# ATESLEME.net
KiCad netlist of a schematic drawn in EAGLE
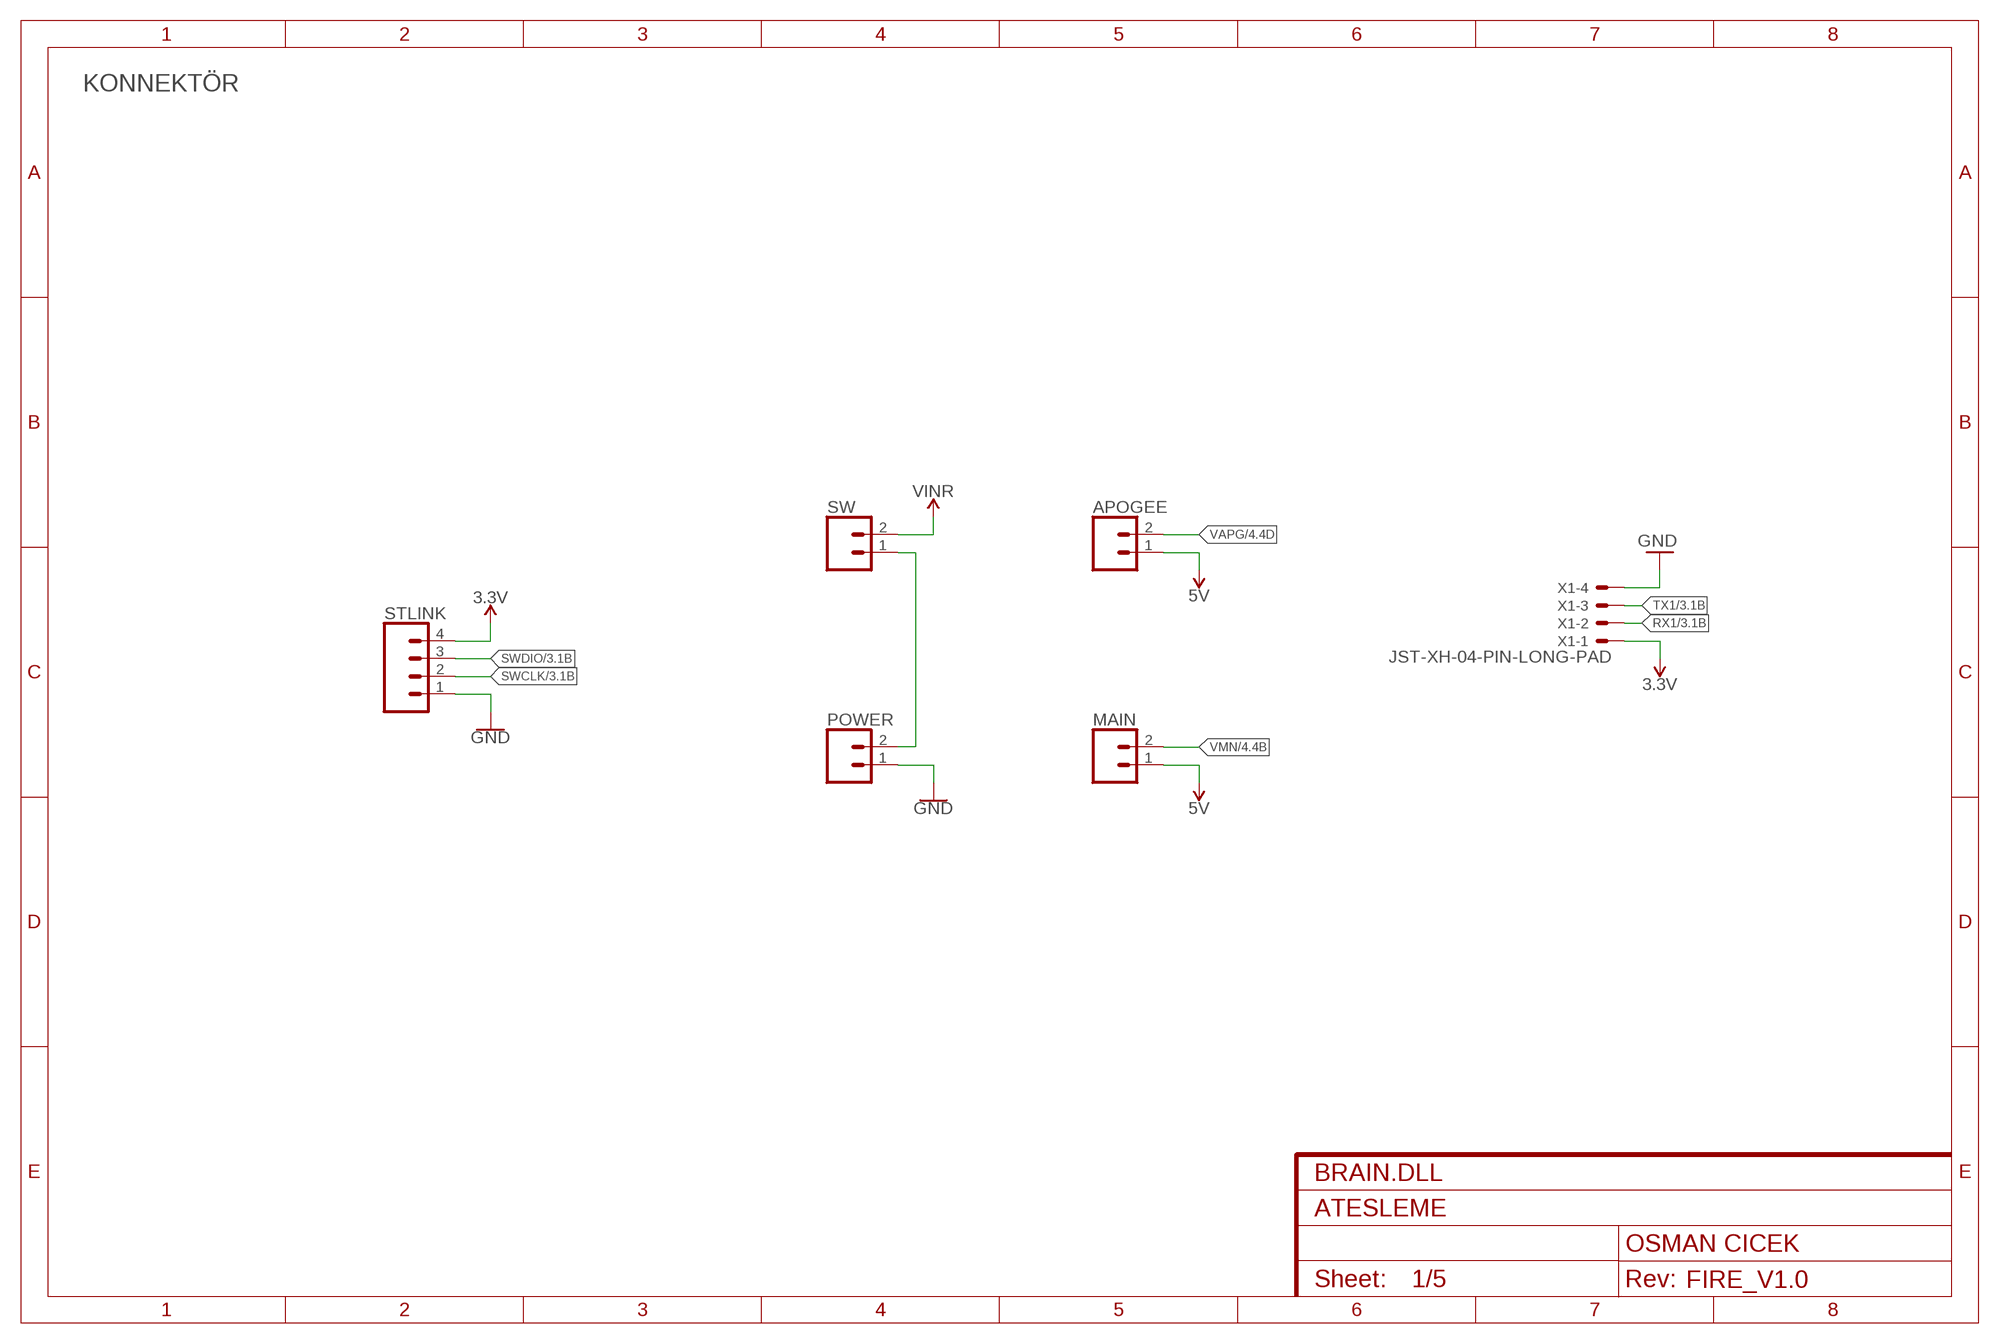
[diagram p0: schematic, sheet 1]
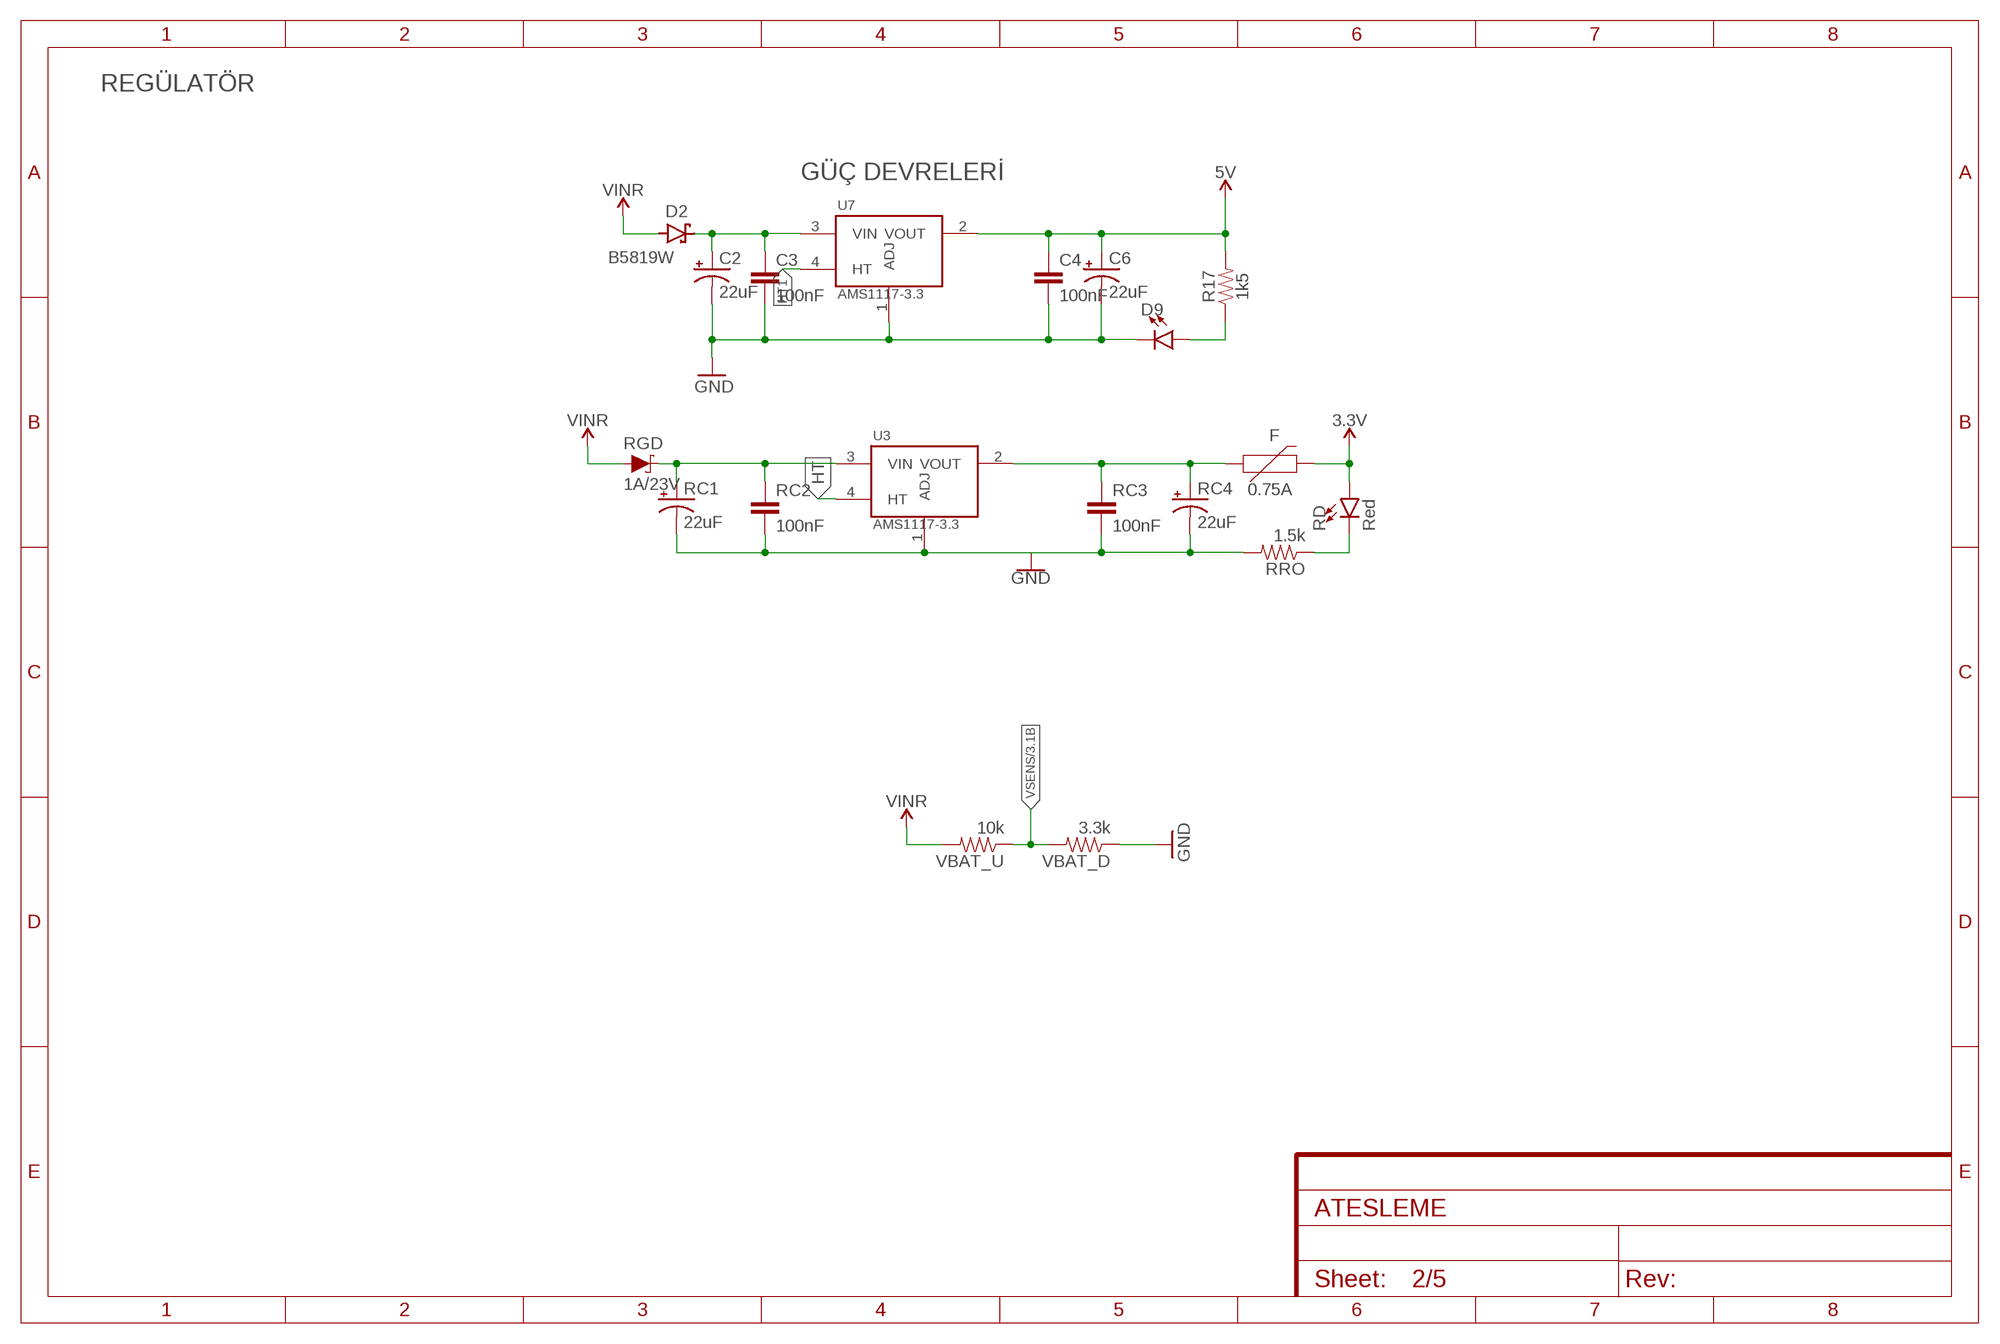
[diagram p1: schematic, sheet 2]
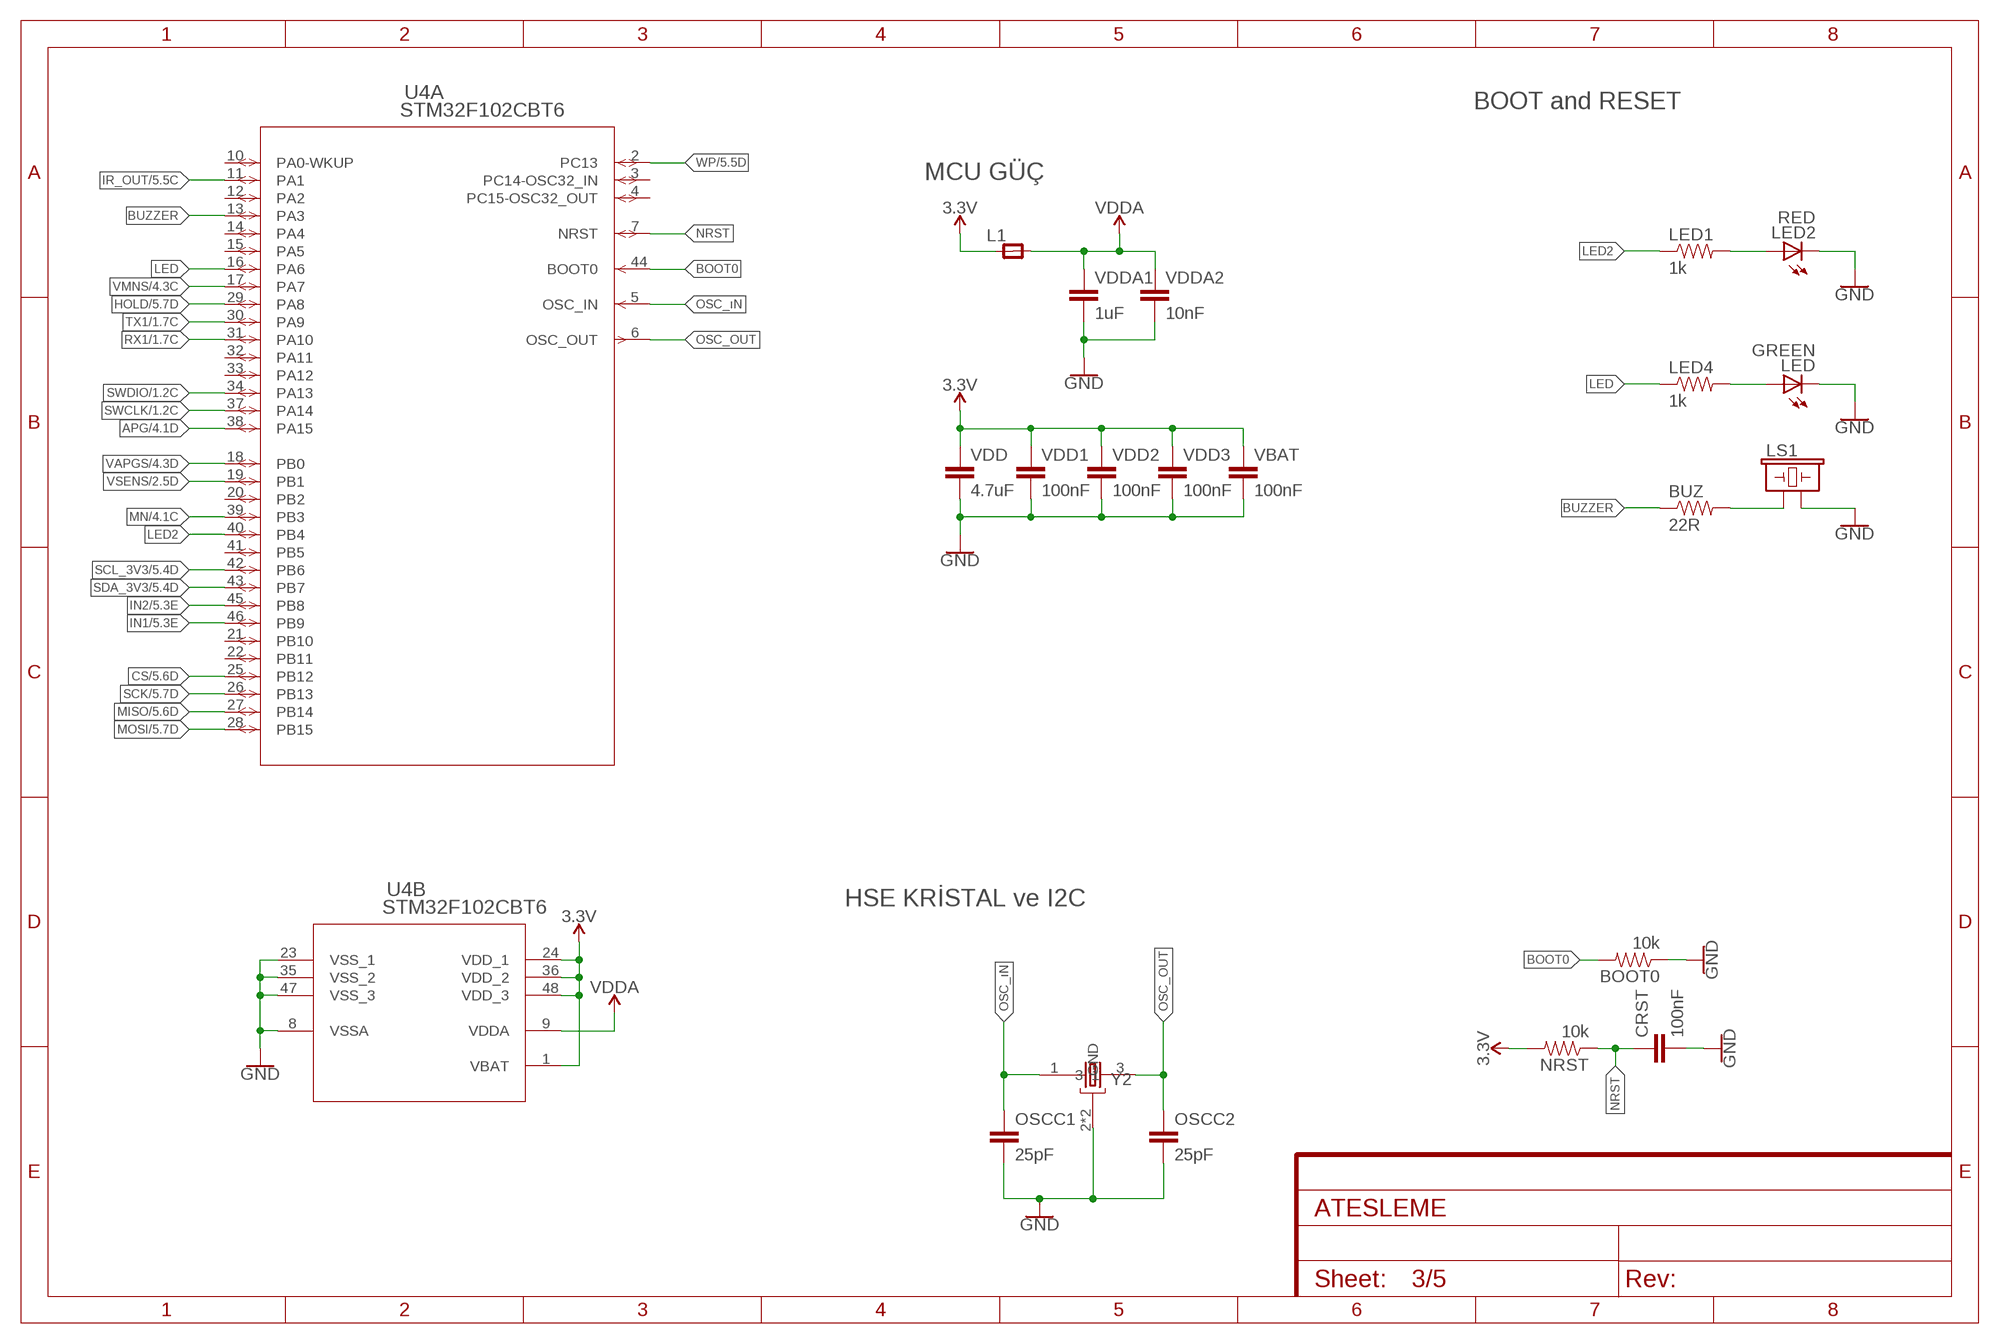
[diagram p2: schematic, sheet 3]
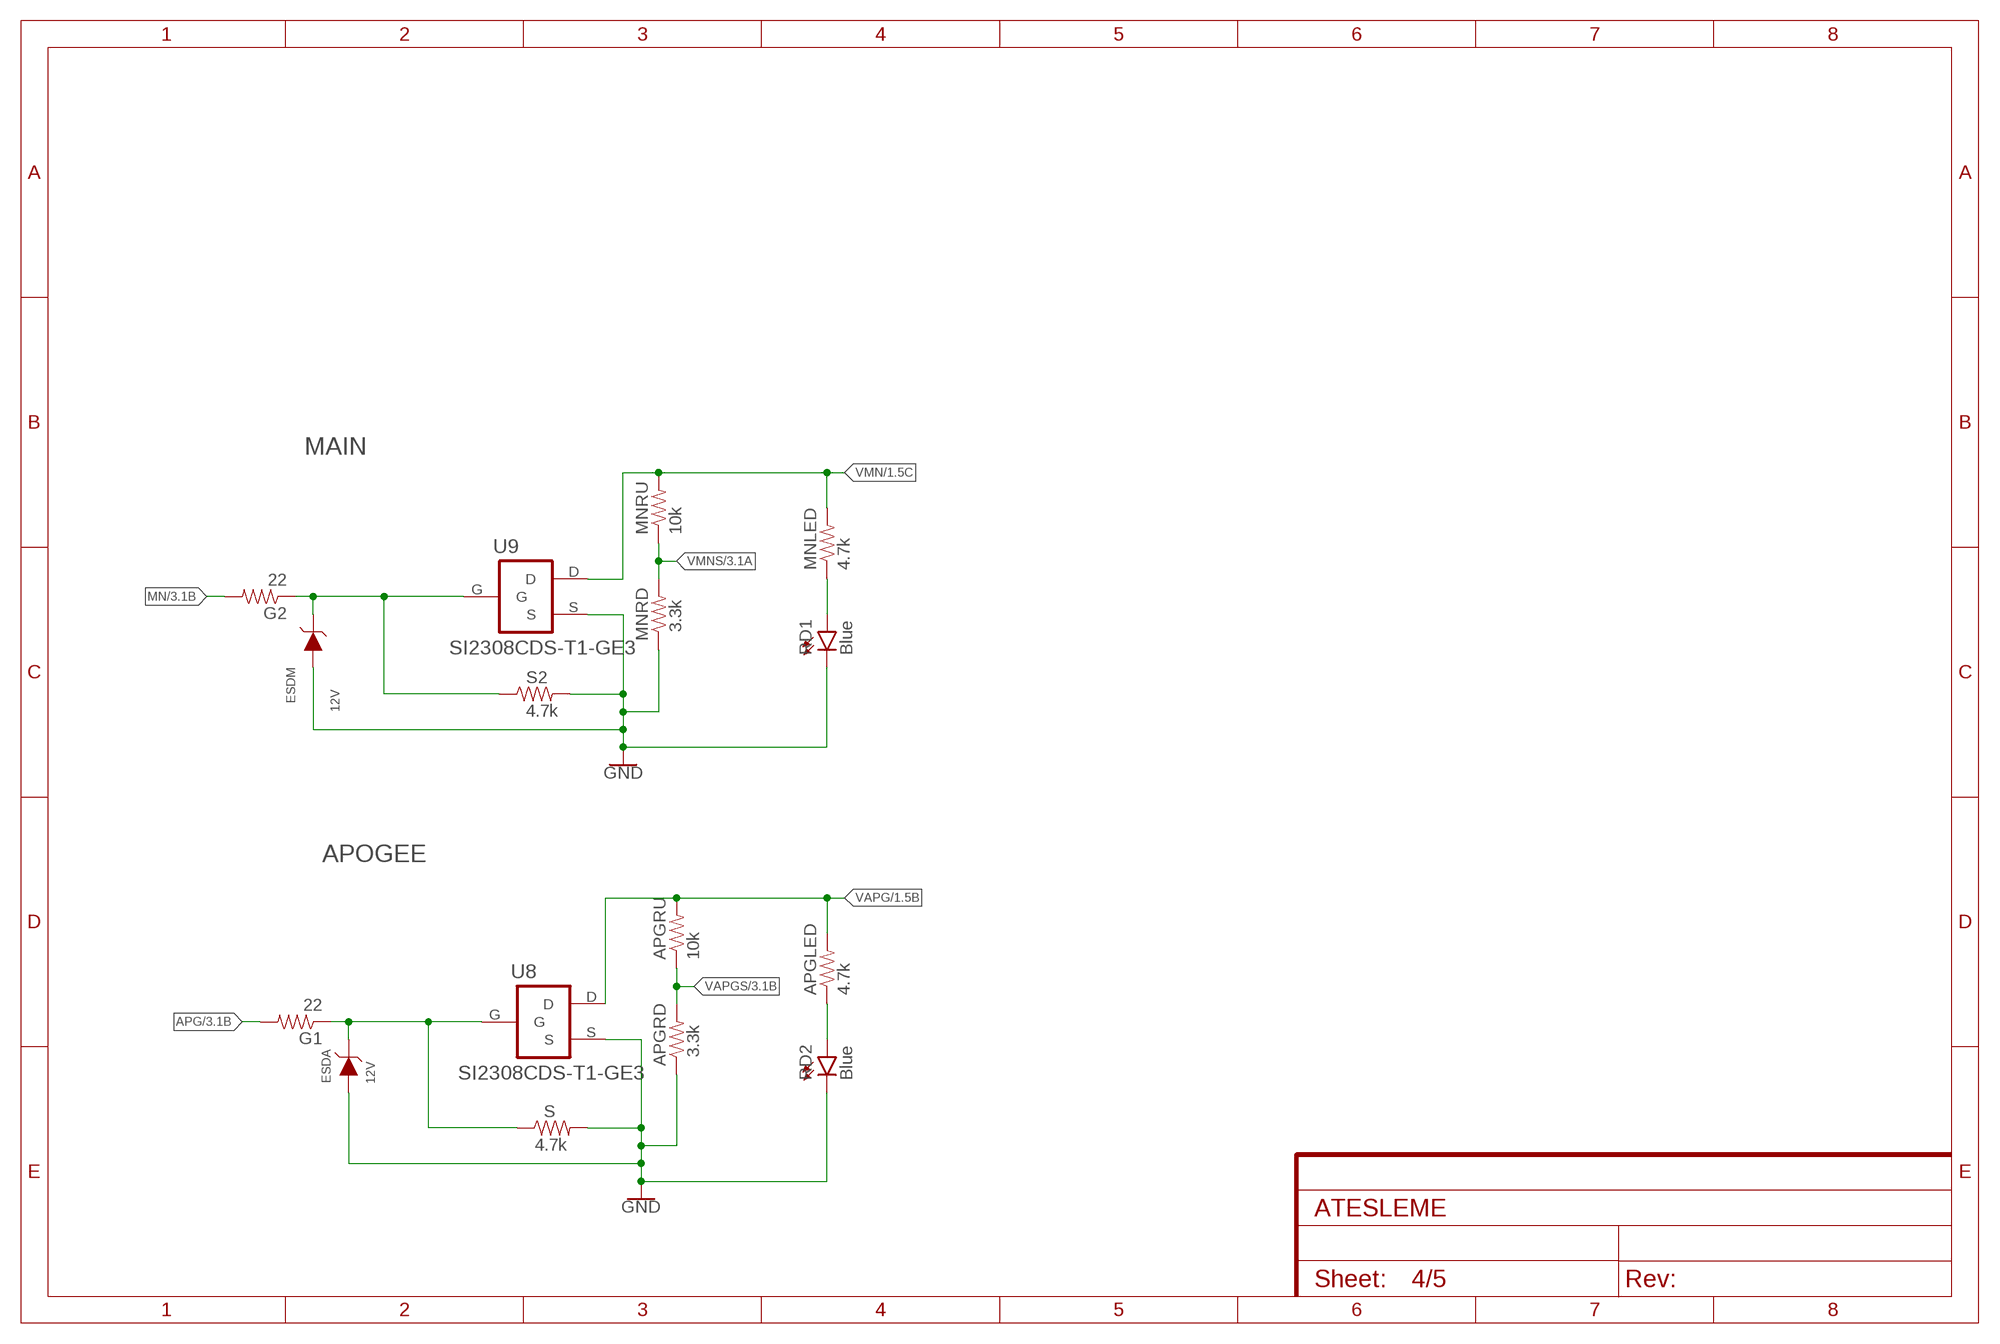
[diagram p3: schematic, sheet 4]
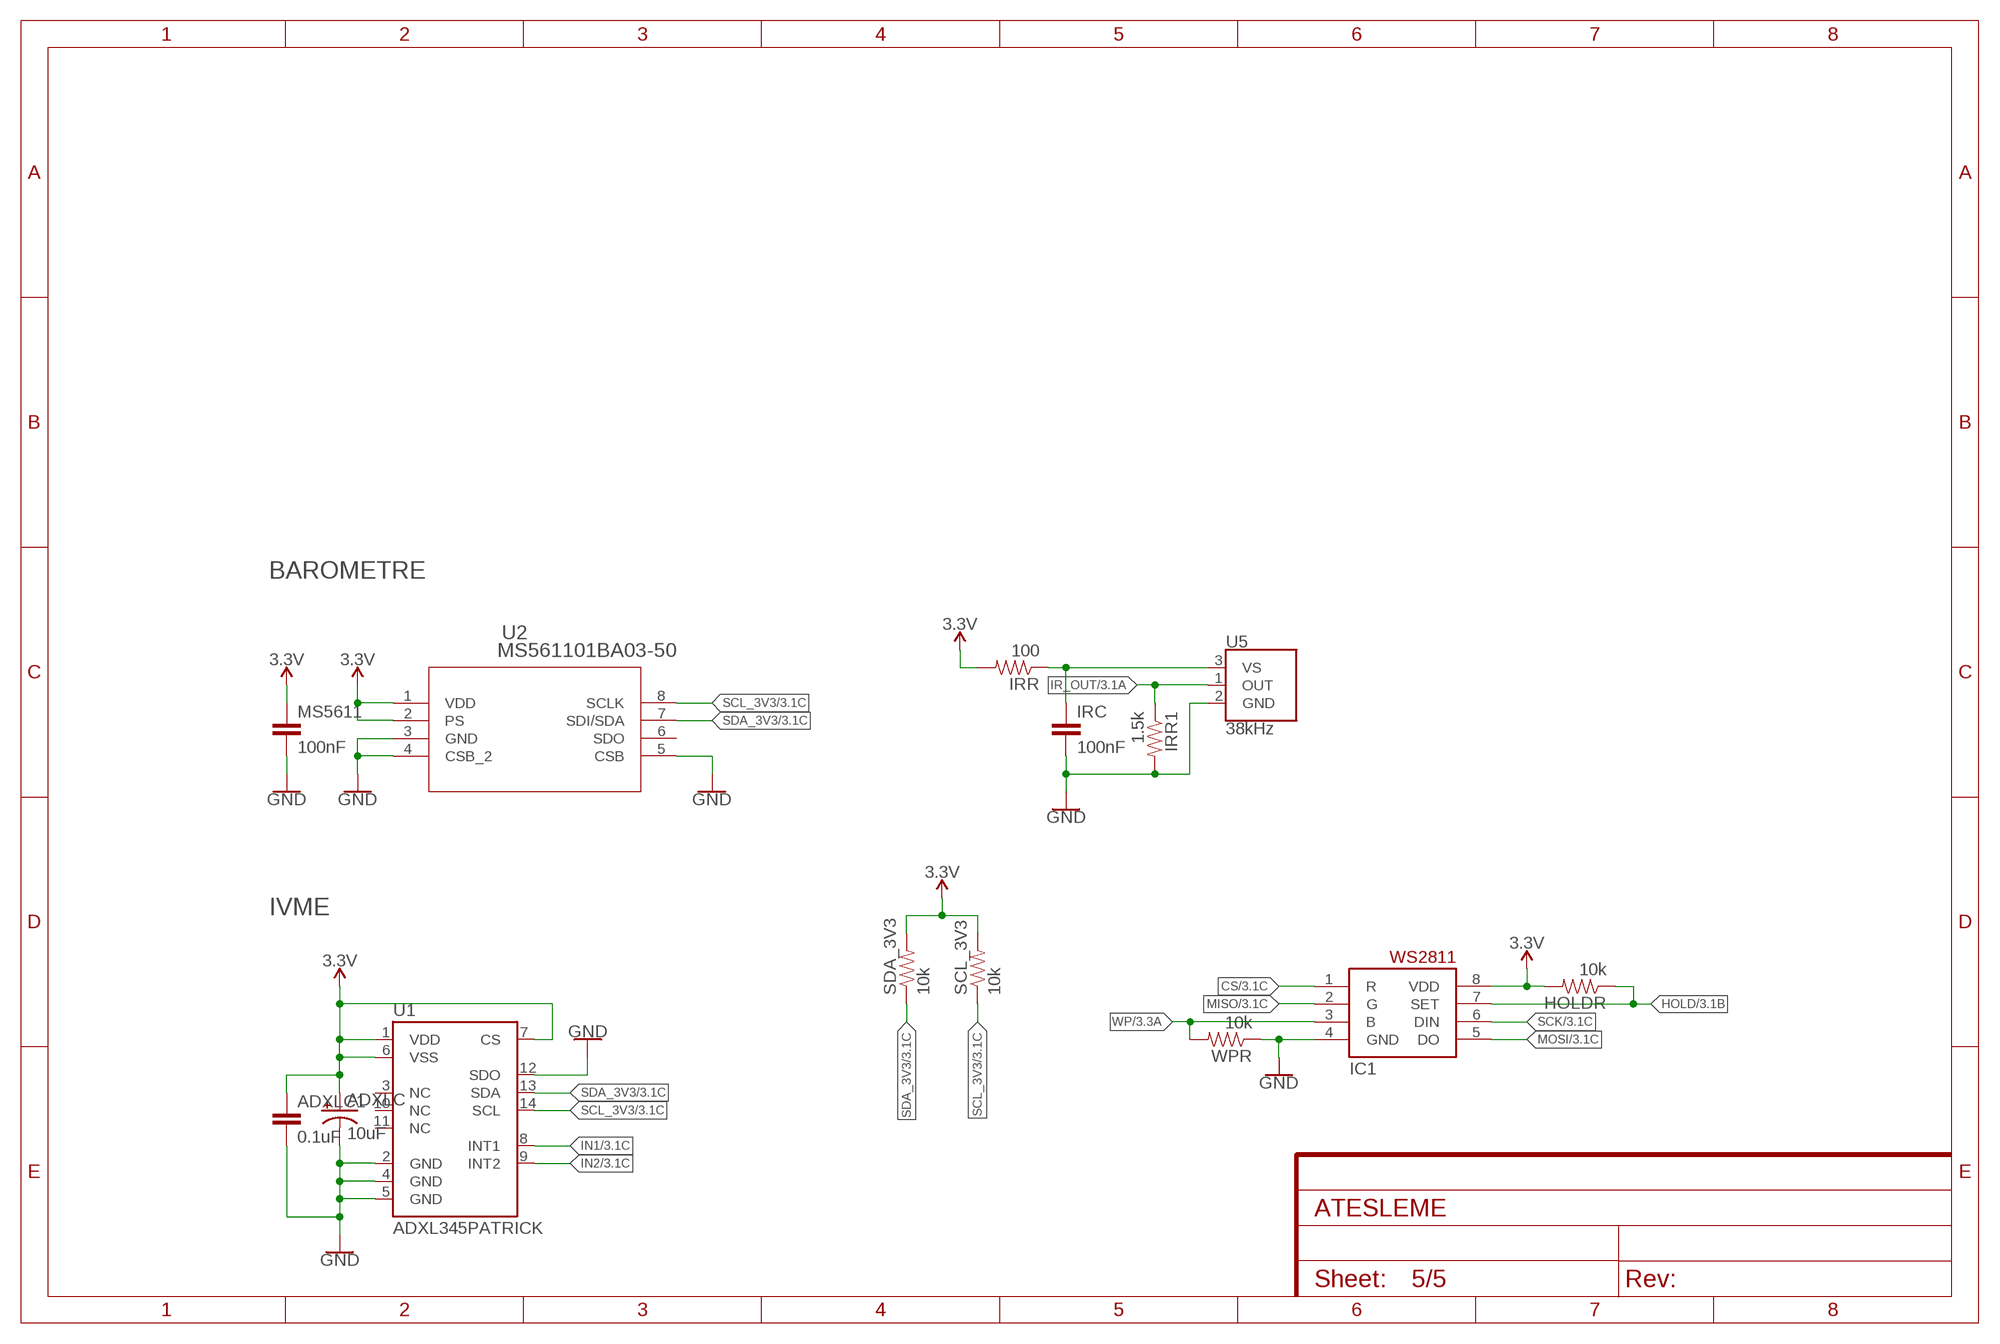
[diagram p4: schematic, sheet 5]

(export (version "E")
  (design (tool "Eeschema 10.0.6"))
  (components
    (comp (ref "APGLED")
      (value "4.7k")
      (footprint "eagle-import:0603-RES")
      (libsource (lib "eagle-import") (part "2.0KOHM1/10W5%(0603)"))
    )
    (comp (ref "APGRD")
      (value "3.3k")
      (footprint "eagle-import:0603-RES")
      (libsource (lib "eagle-import") (part "2.0KOHM1/10W5%(0603)"))
    )
    (comp (ref "APGRU")
      (value "10k")
      (footprint "eagle-import:0603-RES")
      (libsource (lib "eagle-import") (part "2.0KOHM1/10W5%(0603)"))
    )
    (comp (ref "ESDA")
      (value "12V")
      (footprint "eagle-import:WE-TVSP_DO-214AC_UNIDIRECTIONAL")
      (libsource (lib "eagle-import") (part "WE-TVSP_DO-214AC_400W_UNI_824500102"))
    )
    (comp (ref "ESDM")
      (value "12V")
      (footprint "eagle-import:WE-TVSP_DO-214AC_UNIDIRECTIONAL")
      (libsource (lib "eagle-import") (part "WE-TVSP_DO-214AC_400W_UNI_824500102"))
    )
    (comp (ref "G1")
      (value "22")
      (footprint "eagle-import:0603-RES")
      (libsource (lib "eagle-import") (part "2.0KOHM1/10W5%(0603)"))
    )
    (comp (ref "G2")
      (value "22")
      (footprint "eagle-import:0603-RES")
      (libsource (lib "eagle-import") (part "2.0KOHM1/10W5%(0603)"))
    )
    (comp (ref "MNLED")
      (value "4.7k")
      (footprint "eagle-import:0603-RES")
      (libsource (lib "eagle-import") (part "2.0KOHM1/10W5%(0603)"))
    )
    (comp (ref "MNRD")
      (value "3.3k")
      (footprint "eagle-import:0603-RES")
      (libsource (lib "eagle-import") (part "2.0KOHM1/10W5%(0603)"))
    )
    (comp (ref "MNRU")
      (value "10k")
      (footprint "eagle-import:0603-RES")
      (libsource (lib "eagle-import") (part "2.0KOHM1/10W5%(0603)"))
    )
    (comp (ref "RD1")
      (value "Blue")
      (footprint "eagle-import:LED-0603")
      (libsource (lib "eagle-import") (part "LED-RED0603-SMART"))
    )
    (comp (ref "RD2")
      (value "Blue")
      (footprint "eagle-import:LED-0603")
      (libsource (lib "eagle-import") (part "LED-RED0603-SMART"))
    )
    (comp (ref "S")
      (value "4.7k")
      (footprint "eagle-import:0603-RES")
      (libsource (lib "eagle-import") (part "2.0KOHM1/10W5%(0603)"))
    )
    (comp (ref "S2")
      (value "4.7k")
      (footprint "eagle-import:0603-RES")
      (libsource (lib "eagle-import") (part "2.0KOHM1/10W5%(0603)"))
    )
    (comp (ref "U8")
      (value "SI2308CDS-T1-GE3")
      (footprint "eagle-import:SOT95P240X112-3N")
      (fields (field (name "MF") "Infineon Technologies") (field (name "MP") "IRLML6344TRPBF"))
      (libsource (lib "eagle-import") (part "IRLML6344TRPBF"))
    )
    (comp (ref "U9")
      (value "SI2308CDS-T1-GE3")
      (footprint "eagle-import:SOT95P240X112-3N")
      (fields (field (name "MF") "Infineon Technologies") (field (name "MP") "IRLML6344TRPBF"))
      (libsource (lib "eagle-import") (part "IRLML6344TRPBF"))
    )
    (comp (ref "C2")
      (value "22uF")
      (footprint "eagle-import:EIA3528")
      (libsource (lib "eagle-import") (part "47UF-POLAR-EIA3528-10V-10%"))
    )
    (comp (ref "C3")
      (value "100nF")
      (footprint "eagle-import:0603")
      (libsource (lib "eagle-import") (part "1.0UF-0603-16V-10%"))
    )
    (comp (ref "C4")
      (value "100nF")
      (footprint "eagle-import:0603")
      (libsource (lib "eagle-import") (part "1.0UF-0603-16V-10%"))
    )
    (comp (ref "C6")
      (value "22uF")
      (footprint "eagle-import:EIA3528")
      (libsource (lib "eagle-import") (part "47UF-POLAR-EIA3528-10V-10%"))
    )
    (comp (ref "D2")
      (value "B5819W")
      (footprint "eagle-import:SODFL3718X115")
      (fields (field (name "MANUFACTURER") "ON Semiconductor") (field (name "MPN") "MBR0520LT1G"))
      (libsource (lib "eagle-import") (part "SCHOTTKY_DO-219MBR0520LT1G"))
    )
    (comp (ref "D9")
      (value "LED0603")
      (footprint "eagle-import:LED-0603")
      (libsource (lib "eagle-import") (part "LED0603"))
    )
    (comp (ref "F")
      (value "0.75A")
      (footprint "eagle-import:1206")
      (libsource (lib "eagle-import") (part "PPTC_THREE-QUARTER-AMP"))
    )
    (comp (ref "R17")
      (value "1k5")
      (footprint "eagle-import:0603")
      (libsource (lib "eagle-import") (part "1KOHM-0603-1/10W-1%"))
    )
    (comp (ref "RC1")
      (value "22uF")
      (footprint "eagle-import:EIA3528")
      (libsource (lib "eagle-import") (part "10UF-POLAR-EIA3528-20V-10%(TANT)"))
    )
    (comp (ref "RC2")
      (value "100nF")
      (footprint "eagle-import:0603")
      (libsource (lib "eagle-import") (part "0.1UF-0603-25V-(+80/-20%)"))
    )
    (comp (ref "RC3")
      (value "100nF")
      (footprint "eagle-import:0603")
      (libsource (lib "eagle-import") (part "0.1UF-0603-25V-(+80/-20%)"))
    )
    (comp (ref "RC4")
      (value "22uF")
      (footprint "eagle-import:EIA3528")
      (libsource (lib "eagle-import") (part "10UF-POLAR-EIA3528-20V-10%(TANT)"))
    )
    (comp (ref "RD")
      (value "Red")
      (footprint "eagle-import:LED-0603")
      (libsource (lib "eagle-import") (part "LED-RED0603-SMART"))
    )
    (comp (ref "RGD")
      (value "1A/23V")
      (footprint "eagle-import:SOD-323")
      (libsource (lib "eagle-import") (part "DIODE-SCHOTTKY-BAT20J"))
    )
    (comp (ref "RRO")
      (value "1.5k")
      (footprint "eagle-import:0603-RES")
      (libsource (lib "eagle-import") (part "2.0KOHM1/10W5%(0603)"))
    )
    (comp (ref "U3")
      (value "AMS1117-3.3")
      (footprint "eagle-import:SOT229P700X180-4N")
      (fields (field (name "MF") "Advanced Monolithic Systems"))
      (libsource (lib "eagle-import") (part "AMS1117-3.3"))
    )
    (comp (ref "U7")
      (value "AMS1117-3.3")
      (footprint "eagle-import:SOT229P700X180-4N")
      (fields (field (name "MF") "Advanced Monolithic Systems"))
      (libsource (lib "eagle-import") (part "AMS1117-3.3"))
    )
    (comp (ref "VBAT_D")
      (value "3.3k")
      (footprint "eagle-import:0603-RES")
      (libsource (lib "eagle-import") (part "2.0KOHM1/10W5%(0603)"))
    )
    (comp (ref "VBAT_U")
      (value "10k")
      (footprint "eagle-import:0603-RES")
      (libsource (lib "eagle-import") (part "2.0KOHM1/10W5%(0603)"))
    )
    (comp (ref "BOOT0")
      (value "10k")
      (footprint "eagle-import:0603-RES")
      (libsource (lib "eagle-import") (part "2.0KOHM1/10W5%(0603)"))
    )
    (comp (ref "BUZ")
      (value "22R")
      (footprint "eagle-import:0603-RES")
      (libsource (lib "eagle-import") (part "2.0KOHM1/10W5%(0603)"))
    )
    (comp (ref "CRST")
      (value "100nF")
      (footprint "eagle-import:0603")
      (libsource (lib "eagle-import") (part "0.1UF-0603-25V-(+80/-20%)"))
    )
    (comp (ref "L1")
      (value "RC-MASTER-SMD_FB_0805MP")
      (footprint "eagle-import:RC-MASTER-SMD_L0805MP")
      (libsource (lib "eagle-import") (part "RC-MASTER-SMD_FB_0805MP"))
    )
    (comp (ref "LED")
      (value "GREEN")
      (footprint "eagle-import:LED-0603")
      (libsource (lib "eagle-import") (part "LED-RED0603"))
    )
    (comp (ref "LED1")
      (value "1k")
      (footprint "eagle-import:0603-RES")
      (libsource (lib "eagle-import") (part "2.0KOHM1/10W5%(0603)"))
    )
    (comp (ref "LED2")
      (value "RED")
      (footprint "eagle-import:LED-0603")
      (libsource (lib "eagle-import") (part "LED-RED0603"))
    )
    (comp (ref "LED4")
      (value "1k")
      (footprint "eagle-import:0603-RES")
      (libsource (lib "eagle-import") (part "2.0KOHM1/10W5%(0603)"))
    )
    (comp (ref "LS1")
      (value "BUZZER-PTH")
      (footprint "eagle-import:BUZZER-12MM")
      (libsource (lib "eagle-import") (part "BUZZER-PTH"))
    )
    (comp (ref "NRST")
      (value "10k")
      (footprint "eagle-import:0603-RES")
      (libsource (lib "eagle-import") (part "2.0KOHM1/10W5%(0603)"))
    )
    (comp (ref "OSCC1")
      (value "25pF")
      (footprint "eagle-import:0603")
      (libsource (lib "eagle-import") (part "0.1UF-0603-25V-(+80/-20%)"))
    )
    (comp (ref "OSCC2")
      (value "25pF")
      (footprint "eagle-import:0603")
      (libsource (lib "eagle-import") (part "0.1UF-0603-25V-(+80/-20%)"))
    )
    (comp (ref "U4")
      (value "STM32F102CBT6")
      (footprint "eagle-import:LQFP48-7X7MM")
      (fields (field (name "COPYRIGHT") "Copyright (C) 2018 Accelerated Designs. All rights reserved"))
      (libsource (lib "eagle-import") (part "STM32F102CBT6"))
    )
    (comp (ref "VBAT")
      (value "100nF")
      (footprint "eagle-import:0603")
      (libsource (lib "eagle-import") (part "0.1UF-0603-25V-(+80/-20%)"))
    )
    (comp (ref "VDD")
      (value "4.7uF")
      (footprint "eagle-import:0603")
      (libsource (lib "eagle-import") (part "0.1UF-0603-25V-(+80/-20%)"))
    )
    (comp (ref "VDD1")
      (value "100nF")
      (footprint "eagle-import:0603")
      (libsource (lib "eagle-import") (part "0.1UF-0603-25V-(+80/-20%)"))
    )
    (comp (ref "VDD2")
      (value "100nF")
      (footprint "eagle-import:0603")
      (libsource (lib "eagle-import") (part "0.1UF-0603-25V-(+80/-20%)"))
    )
    (comp (ref "VDD3")
      (value "100nF")
      (footprint "eagle-import:0603")
      (libsource (lib "eagle-import") (part "0.1UF-0603-25V-(+80/-20%)"))
    )
    (comp (ref "VDDA1")
      (value "1uF")
      (footprint "eagle-import:0603")
      (libsource (lib "eagle-import") (part "0.1UF-0603-25V-(+80/-20%)"))
    )
    (comp (ref "VDDA2")
      (value "10nF")
      (footprint "eagle-import:0603")
      (libsource (lib "eagle-import") (part "0.1UF-0603-25V-(+80/-20%)"))
    )
    (comp (ref "Y2")
      (value "ABM2B-8.000MHZ-10-1-U-T")
      (footprint "eagle-import:OSCCC500X320X110-4N")
      (fields (field (name "MF") "Abracon") (field (name "MP") "ABM3B-26.000MHZ-10-1-U-T"))
      (libsource (lib "eagle-import") (part "ABM3B-26.000MHZ-10-1-U-T"))
    )
    (comp (ref "ADXLC")
      (value "10uF")
      (footprint "eagle-import:EIA3216")
      (libsource (lib "eagle-import") (part "10UF-POLAR-EIA3216-16V-10%(TANT)"))
    )
    (comp (ref "ADXLC1")
      (value "0.1uF")
      (footprint "eagle-import:0603")
      (libsource (lib "eagle-import") (part "0.1UF-0603-25V-(+80/-20%)"))
    )
    (comp (ref "HOLDR")
      (value "10k")
      (footprint "eagle-import:0603-RES")
      (libsource (lib "eagle-import") (part "2.0KOHM1/10W5%(0603)"))
    )
    (comp (ref "IC1")
      (value "EN25F40-100GCP-TR")
      (footprint "eagle-import:SO08-SKINNYPADS")
      (libsource (lib "eagle-import") (part "WS2811-SOP8"))
    )
    (comp (ref "IRC")
      (value "100nF")
      (footprint "eagle-import:0603")
      (libsource (lib "eagle-import") (part "0.1UF-0603-25V-(+80/-20%)"))
    )
    (comp (ref "IRR")
      (value "100")
      (footprint "eagle-import:0603-RES")
      (libsource (lib "eagle-import") (part "2.0KOHM1/10W5%(0603)"))
    )
    (comp (ref "IRR1")
      (value "1.5k")
      (footprint "eagle-import:0603-RES")
      (libsource (lib "eagle-import") (part "2.0KOHM1/10W5%(0603)"))
    )
    (comp (ref "MS5611")
      (value "100nF")
      (footprint "eagle-import:0603")
      (libsource (lib "eagle-import") (part "0.1UF-0603-25V-(+80/-20%)"))
    )
    (comp (ref "SCL_3V3")
      (value "10k")
      (footprint "eagle-import:0603-RES")
      (libsource (lib "eagle-import") (part "2.0KOHM1/10W5%(0603)"))
    )
    (comp (ref "SDA_3V3")
      (value "10k")
      (footprint "eagle-import:0603-RES")
      (libsource (lib "eagle-import") (part "2.0KOHM1/10W5%(0603)"))
    )
    (comp (ref "U1")
      (value "ADXL345PATRICK")
      (footprint "eagle-import:LGA14_1_1_PATRICK")
      (libsource (lib "eagle-import") (part "ADXL345PATRICK"))
    )
    (comp (ref "U2")
      (value "MS561101BA03-50")
      (footprint "eagle-import:SON8_MS5611_TEC")
      (fields (field (name "COPYRIGHT") "Copyright (C) 2016 Accelerated Designs. All rights reserved"))
      (libsource (lib "eagle-import") (part "MS561101BA03-50"))
    )
    (comp (ref "U5")
      (value "38kHz")
      (footprint "eagle-import:TSOP382")
      (libsource (lib "eagle-import") (part "TSOP38238"))
    )
    (comp (ref "WPR")
      (value "10k")
      (footprint "eagle-import:0603-RES")
      (libsource (lib "eagle-import") (part "2.0KOHM1/10W5%(0603)"))
    )
    (comp (ref "APOGEE")
      (value "CONN_023.5MM-NO_SILK")
      (footprint "eagle-import:SCREWTERMINAL-3.5MM-2-NS")
      (libsource (lib "eagle-import") (part "CONN_023.5MM-NO_SILK"))
    )
    (comp (ref "MAIN")
      (value "CONN_023.5MM-NO_SILK")
      (footprint "eagle-import:SCREWTERMINAL-3.5MM-2-NS")
      (libsource (lib "eagle-import") (part "CONN_023.5MM-NO_SILK"))
    )
    (comp (ref "POWER")
      (value "CONN_023.5MM-NO_SILK")
      (footprint "eagle-import:SCREWTERMINAL-3.5MM-2-NS")
      (libsource (lib "eagle-import") (part "CONN_023.5MM-NO_SILK"))
    )
    (comp (ref "STLINK")
      (value "CONN_04")
      (footprint "eagle-import:1X04")
      (libsource (lib "eagle-import") (part "CONN_04"))
    )
    (comp (ref "SW")
      (value "CONN_023.5MM-NO_SILK")
      (footprint "eagle-import:SCREWTERMINAL-3.5MM-2-NS")
      (libsource (lib "eagle-import") (part "CONN_023.5MM-NO_SILK"))
    )
    (comp (ref "X1")
      (value "JST-XH-04-PIN-LONG-PAD")
      (footprint "eagle-import:JST-XH-04-PACKAGE-LONG-PAD")
      (libsource (lib "eagle-import") (part "JST-XH-04-PIN-LONG-PAD"))
    )
  )
  (nets
    (net (code "1") (name "3.3V") (class "Default")
      (node (ref "ADXLC") (pin "+") (pinfunction "+_+") (pintype "passive"))
      (node (ref "ADXLC1") (pin "1") (pinfunction "1_1") (pintype "passive"))
      (node (ref "F") (pin "2") (pinfunction "2_2") (pintype "bidirectional"))
      (node (ref "HOLDR") (pin "2") (pinfunction "2_2") (pintype "passive"))
      (node (ref "IC1") (pin "8") (pinfunction "VDD_8") (pintype "power_in"))
      (node (ref "IRR") (pin "2") (pinfunction "2_2") (pintype "passive"))
      (node (ref "L1") (pin "1") (pinfunction "1_1") (pintype "passive"))
      (node (ref "MS5611") (pin "1") (pinfunction "1_1") (pintype "passive"))
      (node (ref "NRST") (pin "2") (pinfunction "2_2") (pintype "passive"))
      (node (ref "RD") (pin "A") (pinfunction "A_A") (pintype "passive"))
      (node (ref "SCL_3V3") (pin "2") (pinfunction "2_2") (pintype "passive"))
      (node (ref "SDA_3V3") (pin "2") (pinfunction "2_2") (pintype "passive"))
      (node (ref "STLINK") (pin "4") (pinfunction "4_4") (pintype "passive"))
      (node (ref "U1") (pin "1") (pinfunction "VDD_1") (pintype "bidirectional"))
      (node (ref "U1") (pin "6") (pinfunction "VSS_6") (pintype "bidirectional"))
      (node (ref "U1") (pin "7") (pinfunction "CS_7") (pintype "bidirectional"))
      (node (ref "U2") (pin "1") (pinfunction "VDD_1") (pintype "power_in"))
      (node (ref "U2") (pin "2") (pinfunction "PS_2") (pintype "input"))
      (node (ref "U4") (pin "1") (pinfunction "VBAT_1") (pintype "power_in"))
      (node (ref "U4") (pin "24") (pinfunction "VDD_1_24") (pintype "power_in"))
      (node (ref "U4") (pin "36") (pinfunction "VDD_2_36") (pintype "power_in"))
      (node (ref "U4") (pin "48") (pinfunction "VDD_3_48") (pintype "power_in"))
      (node (ref "VBAT") (pin "1") (pinfunction "1_1") (pintype "passive"))
      (node (ref "VDD") (pin "1") (pinfunction "1_1") (pintype "passive"))
      (node (ref "VDD1") (pin "1") (pinfunction "1_1") (pintype "passive"))
      (node (ref "VDD2") (pin "1") (pinfunction "1_1") (pintype "passive"))
      (node (ref "VDD3") (pin "1") (pinfunction "1_1") (pintype "passive"))
      (node (ref "X1") (pin "1") (pinfunction "S_1") (pintype "passive"))
    )
    (net (code "2") (name "5V") (class "Default")
      (node (ref "APOGEE") (pin "1") (pinfunction "1_1") (pintype "passive"))
      (node (ref "C4") (pin "1") (pinfunction "1_1") (pintype "passive"))
      (node (ref "C6") (pin "A") (pinfunction "+_A") (pintype "passive"))
      (node (ref "MAIN") (pin "1") (pinfunction "1_1") (pintype "passive"))
      (node (ref "R17") (pin "2") (pinfunction "2_2") (pintype "passive"))
      (node (ref "U7") (pin "2") (pinfunction "VOUT_2") (pintype "output"))
    )
    (net (code "3") (name "APG") (class "Default")
      (node (ref "G1") (pin "2") (pinfunction "2_2") (pintype "passive"))
      (node (ref "U4") (pin "38") (pinfunction "PA15_38") (pintype "bidirectional"))
    )
    (net (code "4") (name "BOOT0") (class "Default")
      (node (ref "BOOT0") (pin "2") (pinfunction "2_2") (pintype "passive"))
      (node (ref "U4") (pin "44") (pinfunction "BOOT0_44") (pintype "input"))
    )
    (net (code "5") (name "BUZZER") (class "Default")
      (node (ref "BUZ") (pin "1") (pinfunction "1_1") (pintype "passive"))
      (node (ref "U4") (pin "13") (pinfunction "PA3_13") (pintype "bidirectional"))
    )
    (net (code "6") (name "CS") (class "Default")
      (node (ref "IC1") (pin "1") (pinfunction "R_1") (pintype "open_collector"))
      (node (ref "U4") (pin "25") (pinfunction "PB12_25") (pintype "bidirectional"))
    )
    (net (code "7") (name "GND") (class "Default")
      (node (ref "ADXLC") (pin "-") (pinfunction "-_-") (pintype "passive"))
      (node (ref "ADXLC1") (pin "2") (pinfunction "2_2") (pintype "passive"))
      (node (ref "APGRD") (pin "1") (pinfunction "1_1") (pintype "passive"))
      (node (ref "BOOT0") (pin "1") (pinfunction "1_1") (pintype "passive"))
      (node (ref "C2") (pin "C") (pinfunction "-_C") (pintype "passive"))
      (node (ref "C3") (pin "2") (pinfunction "2_2") (pintype "passive"))
      (node (ref "C4") (pin "2") (pinfunction "2_2") (pintype "passive"))
      (node (ref "C6") (pin "C") (pinfunction "-_C") (pintype "passive"))
      (node (ref "CRST") (pin "2") (pinfunction "2_2") (pintype "passive"))
      (node (ref "D9") (pin "C") (pinfunction "C_C") (pintype "passive"))
      (node (ref "ESDA") (pin "2") (pinfunction "A_2") (pintype "passive"))
      (node (ref "ESDM") (pin "2") (pinfunction "A_2") (pintype "passive"))
      (node (ref "IC1") (pin "4") (pinfunction "GND_4") (pintype "power_in"))
      (node (ref "IRC") (pin "2") (pinfunction "2_2") (pintype "passive"))
      (node (ref "IRR1") (pin "2") (pinfunction "2_2") (pintype "passive"))
      (node (ref "LED") (pin "C") (pinfunction "C_C") (pintype "passive"))
      (node (ref "LED2") (pin "C") (pinfunction "C_C") (pintype "passive"))
      (node (ref "LS1") (pin "-") (pinfunction "2_-") (pintype "passive"))
      (node (ref "MNRD") (pin "1") (pinfunction "1_1") (pintype "passive"))
      (node (ref "MS5611") (pin "2") (pinfunction "2_2") (pintype "passive"))
      (node (ref "OSCC1") (pin "2") (pinfunction "2_2") (pintype "passive"))
      (node (ref "OSCC2") (pin "2") (pinfunction "2_2") (pintype "passive"))
      (node (ref "POWER") (pin "1") (pinfunction "1_1") (pintype "passive"))
      (node (ref "RC1") (pin "C") (pinfunction "-_C") (pintype "passive"))
      (node (ref "RC2") (pin "2") (pinfunction "2_2") (pintype "passive"))
      (node (ref "RC3") (pin "2") (pinfunction "2_2") (pintype "passive"))
      (node (ref "RC4") (pin "C") (pinfunction "-_C") (pintype "passive"))
      (node (ref "RD1") (pin "C") (pinfunction "C_C") (pintype "passive"))
      (node (ref "RD2") (pin "C") (pinfunction "C_C") (pintype "passive"))
      (node (ref "RRO") (pin "2") (pinfunction "2_2") (pintype "passive"))
      (node (ref "S") (pin "2") (pinfunction "2_2") (pintype "passive"))
      (node (ref "S2") (pin "2") (pinfunction "2_2") (pintype "passive"))
      (node (ref "STLINK") (pin "1") (pinfunction "1_1") (pintype "passive"))
      (node (ref "U1") (pin "12") (pinfunction "SDO_12") (pintype "bidirectional"))
      (node (ref "U1") (pin "2") (pinfunction "GND_2") (pintype "bidirectional"))
      (node (ref "U1") (pin "4") (pinfunction "GND_4") (pintype "bidirectional"))
      (node (ref "U1") (pin "5") (pinfunction "GND_5") (pintype "bidirectional"))
      (node (ref "U2") (pin "3") (pinfunction "GND_3") (pintype "passive"))
      (node (ref "U2") (pin "4") (pinfunction "CSB_2_4") (pintype "input"))
      (node (ref "U2") (pin "5") (pinfunction "CSB_5") (pintype "input"))
      (node (ref "U3") (pin "1") (pinfunction "ADJ_1") (pintype "power_in"))
      (node (ref "U4") (pin "23") (pinfunction "VSS_1_23") (pintype "power_in"))
      (node (ref "U4") (pin "35") (pinfunction "VSS_2_35") (pintype "power_in"))
      (node (ref "U4") (pin "47") (pinfunction "VSS_3_47") (pintype "power_in"))
      (node (ref "U4") (pin "8") (pinfunction "VSSA_8") (pintype "power_in"))
      (node (ref "U5") (pin "2") (pinfunction "GND_2") (pintype "bidirectional"))
      (node (ref "U7") (pin "1") (pinfunction "ADJ_1") (pintype "power_in"))
      (node (ref "U8") (pin "S") (pinfunction "S_S") (pintype "passive"))
      (node (ref "U9") (pin "S") (pinfunction "S_S") (pintype "passive"))
      (node (ref "VBAT") (pin "2") (pinfunction "2_2") (pintype "passive"))
      (node (ref "VBAT_D") (pin "1") (pinfunction "1_1") (pintype "passive"))
      (node (ref "VDD") (pin "2") (pinfunction "2_2") (pintype "passive"))
      (node (ref "VDD1") (pin "2") (pinfunction "2_2") (pintype "passive"))
      (node (ref "VDD2") (pin "2") (pinfunction "2_2") (pintype "passive"))
      (node (ref "VDD3") (pin "2") (pinfunction "2_2") (pintype "passive"))
      (node (ref "VDDA1") (pin "2") (pinfunction "2_2") (pintype "passive"))
      (node (ref "VDDA2") (pin "2") (pinfunction "2_2") (pintype "passive"))
      (node (ref "WPR") (pin "1") (pinfunction "1_1") (pintype "passive"))
      (node (ref "X1") (pin "4") (pinfunction "S_4") (pintype "passive"))
      (node (ref "Y2") (pin "2") (pinfunction "GND_2") (pintype "passive"))
      (node (ref "Y2") (pin "4") (pinfunction "GND_4") (pintype "passive"))
    )
    (net (code "8") (name "HOLD") (class "Default")
      (node (ref "HOLDR") (pin "1") (pinfunction "1_1") (pintype "passive"))
      (node (ref "IC1") (pin "7") (pinfunction "SET_7") (pintype "input"))
      (node (ref "U4") (pin "29") (pinfunction "PA8_29") (pintype "bidirectional"))
    )
    (net (code "9") (name "HT") (class "Default")
      (node (ref "U3") (pin "4") (pinfunction "HT_4") (pintype "bidirectional"))
    )
    (net (code "10") (name "HT1") (class "Default")
      (node (ref "U7") (pin "4") (pinfunction "HT_4") (pintype "bidirectional"))
    )
    (net (code "11") (name "IN1") (class "Default")
      (node (ref "U1") (pin "8") (pinfunction "INT1_8") (pintype "bidirectional"))
      (node (ref "U4") (pin "46") (pinfunction "PB9_46") (pintype "bidirectional"))
    )
    (net (code "12") (name "IN2") (class "Default")
      (node (ref "U1") (pin "9") (pinfunction "INT2_9") (pintype "bidirectional"))
      (node (ref "U4") (pin "45") (pinfunction "PB8_45") (pintype "bidirectional"))
    )
    (net (code "13") (name "IR_OUT") (class "Default")
      (node (ref "IRR1") (pin "1") (pinfunction "1_1") (pintype "passive"))
      (node (ref "U4") (pin "11") (pinfunction "PA1_11") (pintype "bidirectional"))
      (node (ref "U5") (pin "1") (pinfunction "OUT_1") (pintype "bidirectional"))
    )
    (net (code "14") (name "LED") (class "Default")
      (node (ref "LED4") (pin "1") (pinfunction "1_1") (pintype "passive"))
      (node (ref "U4") (pin "16") (pinfunction "PA6_16") (pintype "bidirectional"))
    )
    (net (code "15") (name "LED2") (class "Default")
      (node (ref "LED1") (pin "1") (pinfunction "1_1") (pintype "passive"))
      (node (ref "U4") (pin "40") (pinfunction "PB4_40") (pintype "bidirectional"))
    )
    (net (code "16") (name "MISO") (class "Default")
      (node (ref "IC1") (pin "2") (pinfunction "G_2") (pintype "open_collector"))
      (node (ref "U4") (pin "27") (pinfunction "PB14_27") (pintype "bidirectional"))
    )
    (net (code "17") (name "MN") (class "Default")
      (node (ref "G2") (pin "2") (pinfunction "2_2") (pintype "passive"))
      (node (ref "U4") (pin "39") (pinfunction "PB3_39") (pintype "bidirectional"))
    )
    (net (code "18") (name "MOSI") (class "Default")
      (node (ref "IC1") (pin "5") (pinfunction "DO_5") (pintype "output"))
      (node (ref "U4") (pin "28") (pinfunction "PB15_28") (pintype "bidirectional"))
    )
    (net (code "19") (name "NRST") (class "Default")
      (node (ref "CRST") (pin "1") (pinfunction "1_1") (pintype "passive"))
      (node (ref "NRST") (pin "1") (pinfunction "1_1") (pintype "passive"))
      (node (ref "U4") (pin "7") (pinfunction "NRST_7") (pintype "bidirectional"))
    )
    (net (code "20") (name "Net-(APGLED-Pad1)") (class "Default")
      (node (ref "APGLED") (pin "1") (pinfunction "1_1") (pintype "passive"))
      (node (ref "RD2") (pin "A") (pinfunction "A_A") (pintype "passive"))
    )
    (net (code "21") (name "Net-(C2-+)") (class "Default")
      (node (ref "C2") (pin "A") (pinfunction "+_A") (pintype "passive"))
      (node (ref "C3") (pin "1") (pinfunction "1_1") (pintype "passive"))
      (node (ref "D2") (pin "1") (pinfunction "C_1") (pintype "passive"))
      (node (ref "U7") (pin "3") (pinfunction "VIN_3") (pintype "input"))
    )
    (net (code "22") (name "Net-(D9-PadA)") (class "Default")
      (node (ref "D9") (pin "A") (pinfunction "A_A") (pintype "passive"))
      (node (ref "R17") (pin "1") (pinfunction "1_1") (pintype "passive"))
    )
    (net (code "23") (name "Net-(ESDA-C)") (class "Default")
      (node (ref "ESDA") (pin "1") (pinfunction "C_1") (pintype "passive"))
      (node (ref "G1") (pin "1") (pinfunction "1_1") (pintype "passive"))
      (node (ref "S") (pin "1") (pinfunction "1_1") (pintype "passive"))
      (node (ref "U8") (pin "G") (pinfunction "G_G") (pintype "input"))
    )
    (net (code "24") (name "Net-(ESDM-C)") (class "Default")
      (node (ref "ESDM") (pin "1") (pinfunction "C_1") (pintype "passive"))
      (node (ref "G2") (pin "1") (pinfunction "1_1") (pintype "passive"))
      (node (ref "S2") (pin "1") (pinfunction "1_1") (pintype "passive"))
      (node (ref "U9") (pin "G") (pinfunction "G_G") (pintype "input"))
    )
    (net (code "25") (name "Net-(LED-PadA)") (class "Default")
      (node (ref "LED") (pin "A") (pinfunction "A_A") (pintype "passive"))
      (node (ref "LED4") (pin "2") (pinfunction "2_2") (pintype "passive"))
    )
    (net (code "26") (name "Net-(LED1-Pad2)") (class "Default")
      (node (ref "LED1") (pin "2") (pinfunction "2_2") (pintype "passive"))
      (node (ref "LED2") (pin "A") (pinfunction "A_A") (pintype "passive"))
    )
    (net (code "27") (name "Net-(LS1-1)") (class "Default")
      (node (ref "BUZ") (pin "2") (pinfunction "2_2") (pintype "passive"))
      (node (ref "LS1") (pin "+") (pinfunction "1_+") (pintype "passive"))
    )
    (net (code "28") (name "Net-(MNLED-Pad1)") (class "Default")
      (node (ref "MNLED") (pin "1") (pinfunction "1_1") (pintype "passive"))
      (node (ref "RD1") (pin "A") (pinfunction "A_A") (pintype "passive"))
    )
    (net (code "29") (name "Net-(POWER-Pad2)") (class "Default")
      (node (ref "POWER") (pin "2") (pinfunction "2_2") (pintype "passive"))
      (node (ref "SW") (pin "1") (pinfunction "1_1") (pintype "passive"))
    )
    (net (code "30") (name "Net-(RC1-+)") (class "Default")
      (node (ref "RC1") (pin "A") (pinfunction "+_A") (pintype "passive"))
      (node (ref "RC2") (pin "1") (pinfunction "1_1") (pintype "passive"))
      (node (ref "RGD") (pin "C") (pinfunction "C_C") (pintype "passive"))
      (node (ref "U3") (pin "3") (pinfunction "VIN_3") (pintype "input"))
    )
    (net (code "31") (name "Net-(RC4-+)") (class "Default")
      (node (ref "F") (pin "1") (pinfunction "1_1") (pintype "bidirectional"))
      (node (ref "RC3") (pin "1") (pinfunction "1_1") (pintype "passive"))
      (node (ref "RC4") (pin "A") (pinfunction "+_A") (pintype "passive"))
      (node (ref "U3") (pin "2") (pinfunction "VOUT_2") (pintype "output"))
    )
    (net (code "32") (name "Net-(RD-PadC)") (class "Default")
      (node (ref "RD") (pin "C") (pinfunction "C_C") (pintype "passive"))
      (node (ref "RRO") (pin "1") (pinfunction "1_1") (pintype "passive"))
    )
    (net (code "33") (name "Net-(U5-VS)") (class "Default")
      (node (ref "IRC") (pin "1") (pinfunction "1_1") (pintype "passive"))
      (node (ref "IRR") (pin "1") (pinfunction "1_1") (pintype "passive"))
      (node (ref "U5") (pin "3") (pinfunction "VS_3") (pintype "bidirectional"))
    )
    (net (code "34") (name "OSC_OUT") (class "Default")
      (node (ref "OSCC2") (pin "1") (pinfunction "1_1") (pintype "passive"))
      (node (ref "U4") (pin "6") (pinfunction "OSC_OUT_6") (pintype "output"))
      (node (ref "Y2") (pin "3") (pinfunction "3_3") (pintype "passive"))
    )
    (net (code "35") (name "OSC_ıN") (class "Default")
      (node (ref "OSCC1") (pin "1") (pinfunction "1_1") (pintype "passive"))
      (node (ref "U4") (pin "5") (pinfunction "OSC_IN_5") (pintype "input"))
      (node (ref "Y2") (pin "1") (pinfunction "1_1") (pintype "passive"))
    )
    (net (code "36") (name "RX1") (class "Default")
      (node (ref "U4") (pin "31") (pinfunction "PA10_31") (pintype "bidirectional"))
      (node (ref "X1") (pin "2") (pinfunction "S_2") (pintype "passive"))
    )
    (net (code "37") (name "SCK") (class "Default")
      (node (ref "IC1") (pin "6") (pinfunction "DIN_6") (pintype "input"))
      (node (ref "U4") (pin "26") (pinfunction "PB13_26") (pintype "bidirectional"))
    )
    (net (code "38") (name "SCL_3V3") (class "Default")
      (node (ref "SCL_3V3") (pin "1") (pinfunction "1_1") (pintype "passive"))
      (node (ref "U1") (pin "14") (pinfunction "SCL_14") (pintype "bidirectional"))
      (node (ref "U2") (pin "8") (pinfunction "SCLK_8") (pintype "input"))
      (node (ref "U4") (pin "42") (pinfunction "PB6_42") (pintype "bidirectional"))
    )
    (net (code "39") (name "SDA_3V3") (class "Default")
      (node (ref "SDA_3V3") (pin "1") (pinfunction "1_1") (pintype "passive"))
      (node (ref "U1") (pin "13") (pinfunction "SDA_13") (pintype "bidirectional"))
      (node (ref "U2") (pin "7") (pinfunction "SDI/SDA_7") (pintype "bidirectional"))
      (node (ref "U4") (pin "43") (pinfunction "PB7_43") (pintype "bidirectional"))
    )
    (net (code "40") (name "SWCLK") (class "Default")
      (node (ref "STLINK") (pin "2") (pinfunction "2_2") (pintype "passive"))
      (node (ref "U4") (pin "37") (pinfunction "PA14_37") (pintype "bidirectional"))
    )
    (net (code "41") (name "SWDIO") (class "Default")
      (node (ref "STLINK") (pin "3") (pinfunction "3_3") (pintype "passive"))
      (node (ref "U4") (pin "34") (pinfunction "PA13_34") (pintype "bidirectional"))
    )
    (net (code "42") (name "TX1") (class "Default")
      (node (ref "U4") (pin "30") (pinfunction "PA9_30") (pintype "bidirectional"))
      (node (ref "X1") (pin "3") (pinfunction "S_3") (pintype "passive"))
    )
    (net (code "43") (name "VAPG") (class "Default")
      (node (ref "APGLED") (pin "2") (pinfunction "2_2") (pintype "passive"))
      (node (ref "APGRU") (pin "2") (pinfunction "2_2") (pintype "passive"))
      (node (ref "APOGEE") (pin "2") (pinfunction "2_2") (pintype "passive"))
      (node (ref "U8") (pin "D") (pinfunction "D_D") (pintype "output"))
    )
    (net (code "44") (name "VAPGS") (class "Default")
      (node (ref "APGRD") (pin "2") (pinfunction "2_2") (pintype "passive"))
      (node (ref "APGRU") (pin "1") (pinfunction "1_1") (pintype "passive"))
      (node (ref "U4") (pin "18") (pinfunction "PB0_18") (pintype "bidirectional"))
    )
    (net (code "45") (name "VDDA") (class "Default")
      (node (ref "L1") (pin "2") (pinfunction "2_2") (pintype "passive"))
      (node (ref "U4") (pin "9") (pinfunction "VDDA_9") (pintype "power_in"))
      (node (ref "VDDA1") (pin "1") (pinfunction "1_1") (pintype "passive"))
      (node (ref "VDDA2") (pin "1") (pinfunction "1_1") (pintype "passive"))
    )
    (net (code "46") (name "VIN") (class "Default")
      (node (ref "D2") (pin "2") (pinfunction "A_2") (pintype "passive"))
      (node (ref "RGD") (pin "A") (pinfunction "A_A") (pintype "passive"))
      (node (ref "SW") (pin "2") (pinfunction "2_2") (pintype "passive"))
      (node (ref "VBAT_U") (pin "2") (pinfunction "2_2") (pintype "passive"))
    )
    (net (code "47") (name "VMN") (class "Default")
      (node (ref "MAIN") (pin "2") (pinfunction "2_2") (pintype "passive"))
      (node (ref "MNLED") (pin "2") (pinfunction "2_2") (pintype "passive"))
      (node (ref "MNRU") (pin "2") (pinfunction "2_2") (pintype "passive"))
      (node (ref "U9") (pin "D") (pinfunction "D_D") (pintype "output"))
    )
    (net (code "48") (name "VMNS") (class "Default")
      (node (ref "MNRD") (pin "2") (pinfunction "2_2") (pintype "passive"))
      (node (ref "MNRU") (pin "1") (pinfunction "1_1") (pintype "passive"))
      (node (ref "U4") (pin "17") (pinfunction "PA7_17") (pintype "bidirectional"))
    )
    (net (code "49") (name "VSENS") (class "Default")
      (node (ref "U4") (pin "19") (pinfunction "PB1_19") (pintype "bidirectional"))
      (node (ref "VBAT_D") (pin "2") (pinfunction "2_2") (pintype "passive"))
      (node (ref "VBAT_U") (pin "1") (pinfunction "1_1") (pintype "passive"))
    )
    (net (code "50") (name "WP") (class "Default")
      (node (ref "IC1") (pin "3") (pinfunction "B_3") (pintype "open_collector"))
      (node (ref "U4") (pin "2") (pinfunction "PC13_2") (pintype "bidirectional"))
      (node (ref "WPR") (pin "2") (pinfunction "2_2") (pintype "passive"))
    )
    (net (code "51") (name "unconnected-(U1-NC-Pad3)") (class "Default")
      (node (ref "U1") (pin "3") (pinfunction "NC_3") (pintype "bidirectional"))
    )
    (net (code "52") (name "unconnected-(U1-NC-Pad10)") (class "Default")
      (node (ref "U1") (pin "10") (pinfunction "NC_10") (pintype "bidirectional"))
    )
    (net (code "53") (name "unconnected-(U1-NC-Pad11)") (class "Default")
      (node (ref "U1") (pin "11") (pinfunction "NC_11") (pintype "bidirectional"))
    )
    (net (code "54") (name "unconnected-(U2-SDO-Pad6)") (class "Default")
      (node (ref "U2") (pin "6") (pinfunction "SDO_6") (pintype "output"))
    )
    (net (code "55") (name "unconnected-(U4A-PA0-WKUP-Pad10)") (class "Default")
      (node (ref "U4") (pin "10") (pinfunction "PA0-WKUP_10") (pintype "bidirectional"))
    )
    (net (code "56") (name "unconnected-(U4A-PA2-Pad12)") (class "Default")
      (node (ref "U4") (pin "12") (pinfunction "PA2_12") (pintype "bidirectional"))
    )
    (net (code "57") (name "unconnected-(U4A-PA4-Pad14)") (class "Default")
      (node (ref "U4") (pin "14") (pinfunction "PA4_14") (pintype "bidirectional"))
    )
    (net (code "58") (name "unconnected-(U4A-PA5-Pad15)") (class "Default")
      (node (ref "U4") (pin "15") (pinfunction "PA5_15") (pintype "bidirectional"))
    )
    (net (code "59") (name "unconnected-(U4A-PA11-Pad32)") (class "Default")
      (node (ref "U4") (pin "32") (pinfunction "PA11_32") (pintype "bidirectional"))
    )
    (net (code "60") (name "unconnected-(U4A-PA12-Pad33)") (class "Default")
      (node (ref "U4") (pin "33") (pinfunction "PA12_33") (pintype "bidirectional"))
    )
    (net (code "61") (name "unconnected-(U4A-PB2-Pad20)") (class "Default")
      (node (ref "U4") (pin "20") (pinfunction "PB2_20") (pintype "bidirectional"))
    )
    (net (code "62") (name "unconnected-(U4A-PB5-Pad41)") (class "Default")
      (node (ref "U4") (pin "41") (pinfunction "PB5_41") (pintype "bidirectional"))
    )
    (net (code "63") (name "unconnected-(U4A-PB10-Pad21)") (class "Default")
      (node (ref "U4") (pin "21") (pinfunction "PB10_21") (pintype "bidirectional"))
    )
    (net (code "64") (name "unconnected-(U4A-PB11-Pad22)") (class "Default")
      (node (ref "U4") (pin "22") (pinfunction "PB11_22") (pintype "bidirectional"))
    )
    (net (code "65") (name "unconnected-(U4A-PC14-OSC32_IN-Pad3)") (class "Default")
      (node (ref "U4") (pin "3") (pinfunction "PC14-OSC32_IN_3") (pintype "bidirectional"))
    )
    (net (code "66") (name "unconnected-(U4A-PC15-OSC32_OUT-Pad4)") (class "Default")
      (node (ref "U4") (pin "4") (pinfunction "PC15-OSC32_OUT_4") (pintype "bidirectional"))
    )
  )
)
